# MOSFET_Board.net
KiCad netlist of a schematic drawn in EAGLE
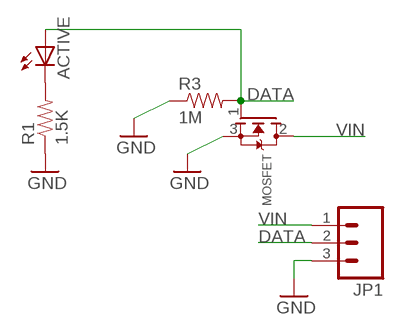
[diagram p0: schematic, sheet 1]

(export (version "E")
  (design (tool "Eeschema 10.0.6"))
  (components
    (comp (ref "ACTIVE")
      (value "LED0603")
      (footprint "eagle-import:LED-0603")
      (libsource (lib "eagle-import") (part "LED0603"))
    )
    (comp (ref "JP1")
      (value "M03POLAR")
      (footprint "eagle-import:MOLEX-1X3")
      (libsource (lib "eagle-import") (part "M03POLAR"))
    )
    (comp (ref "MOSFET")
      (value "MOSFET-NGDS_TO220V")
      (footprint "eagle-import:TO220V")
      (libsource (lib "eagle-import") (part "MOSFET-NGDS_TO220V"))
    )
    (comp (ref "R1")
      (value "1.5K")
      (footprint "eagle-import:1206")
      (libsource (lib "eagle-import") (part "RESISTOR1206"))
    )
    (comp (ref "R3")
      (value "1M")
      (footprint "eagle-import:1206")
      (libsource (lib "eagle-import") (part "RESISTOR1206"))
    )
  )
  (nets
    (net (code "1") (name "/DATA") (class "Default")
      (node (ref "ACTIVE") (pin "A") (pinfunction "A_A") (pintype "passive"))
      (node (ref "JP1") (pin "2") (pinfunction "2_2") (pintype "passive"))
      (node (ref "MOSFET") (pin "1") (pinfunction "G_1") (pintype "bidirectional"))
      (node (ref "R3") (pin "2") (pinfunction "2_2") (pintype "passive"))
    )
    (net (code "2") (name "/VIN") (class "Default")
      (node (ref "JP1") (pin "1") (pinfunction "1_1") (pintype "passive"))
      (node (ref "MOSFET") (pin "2") (pinfunction "D_2") (pintype "bidirectional"))
    )
    (net (code "3") (name "GND") (class "Default")
      (node (ref "JP1") (pin "3") (pinfunction "3_3") (pintype "passive"))
      (node (ref "MOSFET") (pin "3") (pinfunction "S_3") (pintype "bidirectional"))
      (node (ref "R1") (pin "1") (pinfunction "1_1") (pintype "passive"))
      (node (ref "R3") (pin "1") (pinfunction "1_1") (pintype "passive"))
    )
    (net (code "4") (name "Net-(ACTIVE-PadC)") (class "Default")
      (node (ref "ACTIVE") (pin "C") (pinfunction "C_C") (pintype "passive"))
      (node (ref "R1") (pin "2") (pinfunction "2_2") (pintype "passive"))
    )
  )
)
